# 2-mcu.net
KiCad netlist of a schematic drawn in Altium Designer
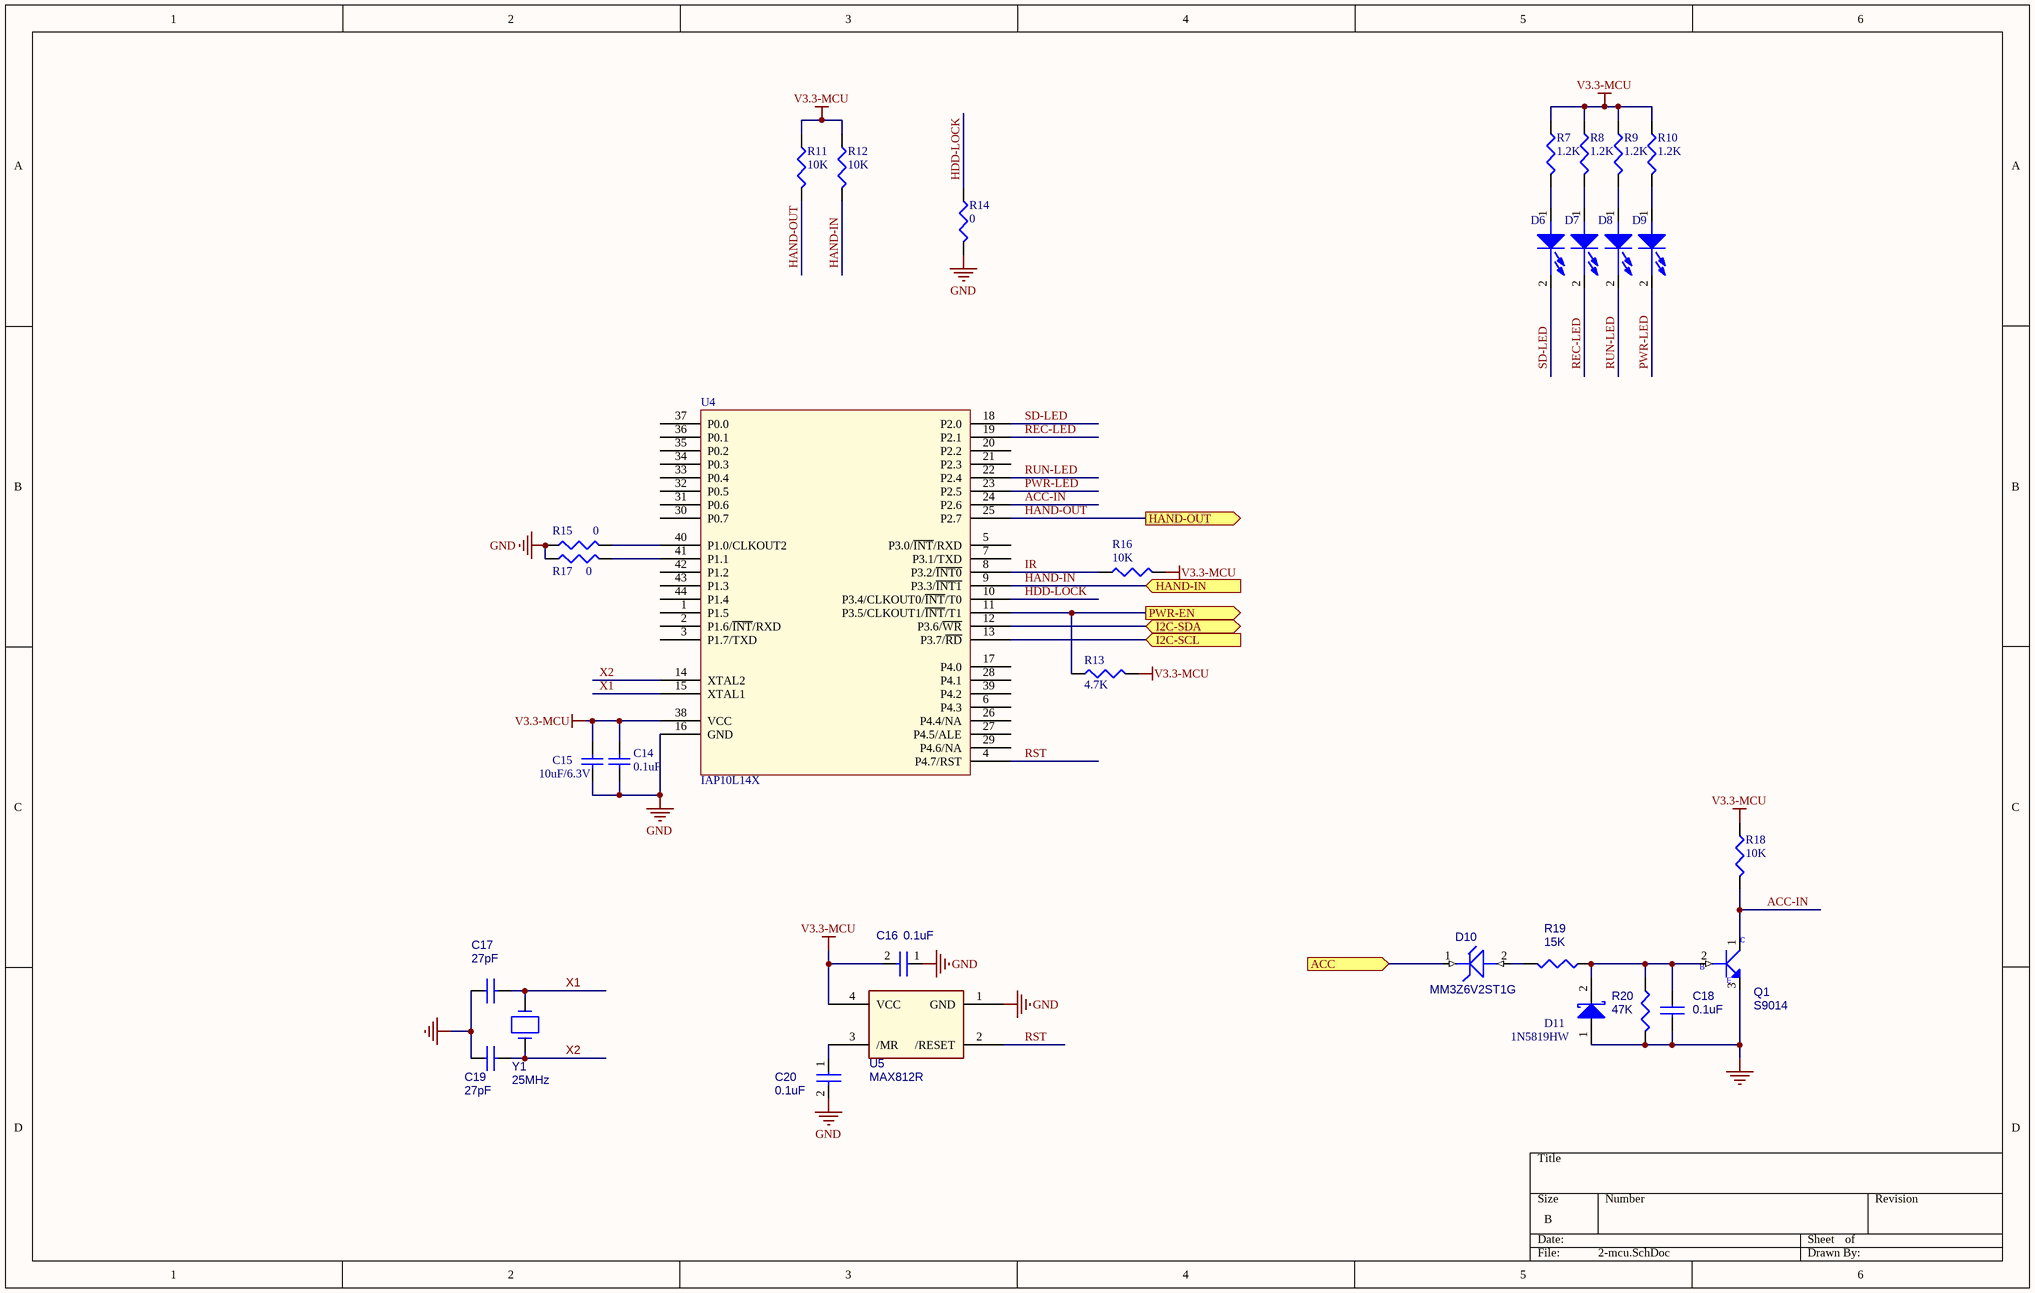
[diagram p0: 2-mcu.SchDoc]

(export (version "E")
  (design (tool "Eeschema 10.0.6"))
  (components
    (comp (ref "C14")
      (value "0.1uF")
      (footprint "0603")
      (description "Capacitor")
      (libsource (lib "Miscellaneous Devices") (part "Cap"))
    )
    (comp (ref "C15")
      (value "10uF/6.3V")
      (footprint "0805")
      (description "Capacitor")
      (libsource (lib "Miscellaneous Devices") (part "Cap"))
    )
    (comp (ref "C16") (value "0.1uF") (libsource (lib "*") (part "CAP NP_Dup2")))
    (comp (ref "C17") (value "27pF") (libsource (lib "*") (part "CAP_Dup1")))
    (comp (ref "C18") (value "0.1uF") (libsource (lib "*") (part "CAP")))
    (comp (ref "C19") (value "27pF") (libsource (lib "*") (part "CAP_Dup1")))
    (comp (ref "C20") (value "0.1uF") (libsource (lib "*") (part "CAP NP_Dup2")))
    (comp (ref "D6") (value "LED GREEN") (footprint "LED0603") (libsource (lib "*") (part "LN01401_1")))
    (comp (ref "D7") (value "LED GREEN") (footprint "LED0603") (libsource (lib "*") (part "LN01401_1")))
    (comp (ref "D8") (value "LED GREEN") (footprint "LED0603") (libsource (lib "*") (part "LN01401_1")))
    (comp (ref "D9") (value "LED GREEN") (footprint "LED0603") (libsource (lib "*") (part "LN01401_1")))
    (comp (ref "D10")
      (value "MM3Z6V2ST1G")
      (footprint "MM3Z5V1ST1G")
      (libsource (lib "*") (part "MMGZ5231BPTLL34"))
    )
    (comp (ref "D11")
      (value "1N5819HW")
      (footprint "1N5819")
      (description "Schottky Rectifier")
      (libsource (lib "Miscellaneous Devices") (part "Diode 11DQ03"))
    )
    (comp (ref "Q1")
      (value "S9014")
      (footprint "NPN")
      (fields (field (name "PART NUMBER") "SB039040000"))
      (libsource (lib "*") (part "MMBT3904_NL_SOT23-3"))
    )
    (comp (ref "R7") (value "1.2K") (footprint "0603") (libsource (lib "*") (part "CR16-1003FM")))
    (comp (ref "R8") (value "1.2K") (footprint "0603") (libsource (lib "*") (part "CR16-1003FM")))
    (comp (ref "R9") (value "1.2K") (footprint "0603") (libsource (lib "*") (part "CR16-1003FM")))
    (comp (ref "R10") (value "1.2K") (footprint "0603") (libsource (lib "*") (part "CR16-1003FM")))
    (comp (ref "R11") (value "10K") (footprint "0603") (libsource (lib "*") (part "CR16-1003FM")))
    (comp (ref "R12") (value "10K") (footprint "0603") (libsource (lib "*") (part "CR16-1003FM")))
    (comp (ref "R13") (value "4.7K") (footprint "0603") (libsource (lib "*") (part "CR16-1003FM")))
    (comp (ref "R14") (value "0") (footprint "0603") (libsource (lib "*") (part "CR16-1003FM")))
    (comp (ref "R15") (value "0") (footprint "0603") (libsource (lib "*") (part "CR16-1003FM")))
    (comp (ref "R16") (value "10K") (footprint "0603") (libsource (lib "*") (part "CR16-1003FM")))
    (comp (ref "R17") (value "0") (footprint "0603") (libsource (lib "*") (part "CR16-1003FM")))
    (comp (ref "R18") (value "10K") (footprint "0603") (libsource (lib "*") (part "CR16-1003FM")))
    (comp (ref "R19") (value "15K") (libsource (lib "*") (part "R")))
    (comp (ref "R20") (value "47K") (libsource (lib "*") (part "R")))
    (comp (ref "U4") (value "IAP10L14X") (footprint "LQFP44") (libsource (lib "Schlib") (part "IAP10L14X")))
    (comp (ref "U5") (value "MAX812R") (libsource (lib "*") (part "MAX811")))
    (comp (ref "Y1") (value "25MHz") (libsource (lib "*") (part "CRYSTAL")))
  )
  (nets
    (net (code "1") (name "/ACC") (class "Default")
      (node (ref "D10") (pin "1") (pinfunction "1_1") (pintype "input"))
    )
    (net (code "2") (name "/ACC-IN") (class "Default")
      (node (ref "Q1") (pin "1") (pinfunction "COLLECTOR_1") (pintype "passive"))
      (node (ref "R18") (pin "2") (pinfunction "2_2") (pintype "passive"))
      (node (ref "U4") (pin "24") (pinfunction "P2.6_24") (pintype "passive"))
    )
    (net (code "3") (name "/HAND-IN") (class "Default")
      (node (ref "R12") (pin "2") (pinfunction "2_2") (pintype "passive"))
      (node (ref "U4") (pin "9") (pinfunction "P3.3/~{INT1}_9") (pintype "passive"))
    )
    (net (code "4") (name "/HAND-OUT") (class "Default")
      (node (ref "R11") (pin "2") (pinfunction "2_2") (pintype "passive"))
      (node (ref "U4") (pin "25") (pinfunction "P2.7_25") (pintype "passive"))
    )
    (net (code "5") (name "/HDD-LOCK") (class "Default")
      (node (ref "R14") (pin "1") (pinfunction "1_1") (pintype "passive"))
      (node (ref "U4") (pin "10") (pinfunction "P3.4/CLKOUT0/~{INT}/T0_10") (pintype "passive"))
    )
    (net (code "6") (name "/I2C-SCL") (class "Default")
      (node (ref "U4") (pin "13") (pinfunction "P3.7/~{RD}_13") (pintype "passive"))
    )
    (net (code "7") (name "/I2C-SDA") (class "Default")
      (node (ref "U4") (pin "12") (pinfunction "P3.6/~{WR}_12") (pintype "passive"))
    )
    (net (code "8") (name "/IR") (class "Default")
      (node (ref "R16") (pin "1") (pinfunction "1_1") (pintype "passive"))
      (node (ref "U4") (pin "8") (pinfunction "P3.2/~{INT0}_8") (pintype "passive"))
    )
    (net (code "9") (name "/PWR-EN") (class "Default")
      (node (ref "R13") (pin "1") (pinfunction "1_1") (pintype "passive"))
      (node (ref "U4") (pin "11") (pinfunction "P3.5/CLKOUT1/~{INT}/T1_11") (pintype "passive"))
    )
    (net (code "10") (name "/PWR-LED") (class "Default")
      (node (ref "D9") (pin "2") (pinfunction "CATHODE_2") (pintype "passive"))
      (node (ref "U4") (pin "23") (pinfunction "P2.5_23") (pintype "passive"))
    )
    (net (code "11") (name "/REC-LED") (class "Default")
      (node (ref "D7") (pin "2") (pinfunction "CATHODE_2") (pintype "passive"))
      (node (ref "U4") (pin "19") (pinfunction "P2.1_19") (pintype "passive"))
    )
    (net (code "12") (name "/RST") (class "Default")
      (node (ref "U4") (pin "4") (pinfunction "P4.7/RST_4") (pintype "passive"))
      (node (ref "U5") (pin "2") (pinfunction "/RESET_2") (pintype "passive"))
    )
    (net (code "13") (name "/RUN-LED") (class "Default")
      (node (ref "D8") (pin "2") (pinfunction "CATHODE_2") (pintype "passive"))
      (node (ref "U4") (pin "22") (pinfunction "P2.4_22") (pintype "passive"))
    )
    (net (code "14") (name "/SD-LED") (class "Default")
      (node (ref "D6") (pin "2") (pinfunction "CATHODE_2") (pintype "passive"))
      (node (ref "U4") (pin "18") (pinfunction "P2.0_18") (pintype "passive"))
    )
    (net (code "15") (name "/X1") (class "Default")
      (node (ref "C17") (pin "2") (pinfunction "2_2") (pintype "passive"))
      (node (ref "U4") (pin "15") (pinfunction "XTAL1_15") (pintype "passive"))
      (node (ref "Y1") (pin "2") (pinfunction "2_2") (pintype "passive"))
    )
    (net (code "16") (name "/X2") (class "Default")
      (node (ref "C19") (pin "2") (pinfunction "2_2") (pintype "passive"))
      (node (ref "U4") (pin "14") (pinfunction "XTAL2_14") (pintype "passive"))
      (node (ref "Y1") (pin "1") (pinfunction "1_1") (pintype "passive"))
    )
    (net (code "17") (name "GND") (class "Default")
      (node (ref "C14") (pin "1") (pinfunction "1_1") (pintype "passive"))
      (node (ref "C15") (pin "1") (pinfunction "1_1") (pintype "passive"))
      (node (ref "C16") (pin "1") (pinfunction "1_1") (pintype "passive"))
      (node (ref "C17") (pin "1") (pinfunction "1_1") (pintype "passive"))
      (node (ref "C18") (pin "2") (pinfunction "2_2") (pintype "passive"))
      (node (ref "C19") (pin "1") (pinfunction "1_1") (pintype "passive"))
      (node (ref "C20") (pin "2") (pinfunction "2_2") (pintype "passive"))
      (node (ref "D11") (pin "1") (pinfunction "A_1") (pintype "passive"))
      (node (ref "Q1") (pin "3") (pinfunction "EMITTER_3") (pintype "passive"))
      (node (ref "R14") (pin "2") (pinfunction "2_2") (pintype "passive"))
      (node (ref "R15") (pin "1") (pinfunction "1_1") (pintype "passive"))
      (node (ref "R17") (pin "1") (pinfunction "1_1") (pintype "passive"))
      (node (ref "R20") (pin "2") (pinfunction "2_2") (pintype "passive"))
      (node (ref "U4") (pin "16") (pinfunction "GND_16") (pintype "passive"))
      (node (ref "U5") (pin "1") (pinfunction "GND_1") (pintype "passive"))
    )
    (net (code "18") (name "Net-(D6-ANODE)") (class "Default")
      (node (ref "D6") (pin "1") (pinfunction "ANODE_1") (pintype "passive"))
      (node (ref "R7") (pin "2") (pinfunction "2_2") (pintype "passive"))
    )
    (net (code "19") (name "Net-(D7-ANODE)") (class "Default")
      (node (ref "D7") (pin "1") (pinfunction "ANODE_1") (pintype "passive"))
      (node (ref "R8") (pin "2") (pinfunction "2_2") (pintype "passive"))
    )
    (net (code "20") (name "Net-(D8-ANODE)") (class "Default")
      (node (ref "D8") (pin "1") (pinfunction "ANODE_1") (pintype "passive"))
      (node (ref "R9") (pin "2") (pinfunction "2_2") (pintype "passive"))
    )
    (net (code "21") (name "Net-(D9-ANODE)") (class "Default")
      (node (ref "D9") (pin "1") (pinfunction "ANODE_1") (pintype "passive"))
      (node (ref "R10") (pin "2") (pinfunction "2_2") (pintype "passive"))
    )
    (net (code "22") (name "Net-(D10-Pad2)") (class "Default")
      (node (ref "D10") (pin "2") (pinfunction "2_2") (pintype "input"))
      (node (ref "R19") (pin "2") (pinfunction "2_2") (pintype "passive"))
    )
    (net (code "23") (name "Net-(D11-K)") (class "Default")
      (node (ref "C18") (pin "1") (pinfunction "1_1") (pintype "passive"))
      (node (ref "D11") (pin "2") (pinfunction "K_2") (pintype "passive"))
      (node (ref "Q1") (pin "2") (pinfunction "BASE_2") (pintype "input"))
      (node (ref "R19") (pin "1") (pinfunction "1_1") (pintype "passive"))
      (node (ref "R20") (pin "1") (pinfunction "1_1") (pintype "passive"))
    )
    (net (code "24") (name "Net-(U4-P1.0{slash}CLKOUT2)") (class "Default")
      (node (ref "R15") (pin "2") (pinfunction "2_2") (pintype "passive"))
      (node (ref "U4") (pin "40") (pinfunction "P1.0/CLKOUT2_40") (pintype "passive"))
    )
    (net (code "25") (name "Net-(U4-P1.1)") (class "Default")
      (node (ref "R17") (pin "2") (pinfunction "2_2") (pintype "passive"))
      (node (ref "U4") (pin "41") (pinfunction "P1.1_41") (pintype "passive"))
    )
    (net (code "26") (name "Net-(U5-{slash}MR)") (class "Default")
      (node (ref "C20") (pin "1") (pinfunction "1_1") (pintype "passive"))
      (node (ref "U5") (pin "3") (pinfunction "/MR_3") (pintype "passive"))
    )
    (net (code "27") (name "V3.3-MCU") (class "Default")
      (node (ref "C14") (pin "2") (pinfunction "2_2") (pintype "passive"))
      (node (ref "C15") (pin "2") (pinfunction "2_2") (pintype "passive"))
      (node (ref "C16") (pin "2") (pinfunction "2_2") (pintype "passive"))
      (node (ref "R10") (pin "1") (pinfunction "1_1") (pintype "passive"))
      (node (ref "R11") (pin "1") (pinfunction "1_1") (pintype "passive"))
      (node (ref "R12") (pin "1") (pinfunction "1_1") (pintype "passive"))
      (node (ref "R13") (pin "2") (pinfunction "2_2") (pintype "passive"))
      (node (ref "R16") (pin "2") (pinfunction "2_2") (pintype "passive"))
      (node (ref "R18") (pin "1") (pinfunction "1_1") (pintype "passive"))
      (node (ref "R7") (pin "1") (pinfunction "1_1") (pintype "passive"))
      (node (ref "R8") (pin "1") (pinfunction "1_1") (pintype "passive"))
      (node (ref "R9") (pin "1") (pinfunction "1_1") (pintype "passive"))
      (node (ref "U4") (pin "38") (pinfunction "VCC_38") (pintype "passive"))
      (node (ref "U5") (pin "4") (pinfunction "VCC_4") (pintype "passive"))
    )
    (net (code "28") (name "unconnected-(U4-P0.0-Pad37)") (class "Default")
      (node (ref "U4") (pin "37") (pinfunction "P0.0_37") (pintype "passive"))
    )
    (net (code "29") (name "unconnected-(U4-P0.1-Pad36)") (class "Default")
      (node (ref "U4") (pin "36") (pinfunction "P0.1_36") (pintype "passive"))
    )
    (net (code "30") (name "unconnected-(U4-P0.2-Pad35)") (class "Default")
      (node (ref "U4") (pin "35") (pinfunction "P0.2_35") (pintype "passive"))
    )
    (net (code "31") (name "unconnected-(U4-P0.3-Pad34)") (class "Default")
      (node (ref "U4") (pin "34") (pinfunction "P0.3_34") (pintype "passive"))
    )
    (net (code "32") (name "unconnected-(U4-P0.4-Pad33)") (class "Default")
      (node (ref "U4") (pin "33") (pinfunction "P0.4_33") (pintype "passive"))
    )
    (net (code "33") (name "unconnected-(U4-P0.5-Pad32)") (class "Default")
      (node (ref "U4") (pin "32") (pinfunction "P0.5_32") (pintype "passive"))
    )
    (net (code "34") (name "unconnected-(U4-P0.6-Pad31)") (class "Default")
      (node (ref "U4") (pin "31") (pinfunction "P0.6_31") (pintype "passive"))
    )
    (net (code "35") (name "unconnected-(U4-P0.7-Pad30)") (class "Default")
      (node (ref "U4") (pin "30") (pinfunction "P0.7_30") (pintype "passive"))
    )
    (net (code "36") (name "unconnected-(U4-P1.2-Pad42)") (class "Default")
      (node (ref "U4") (pin "42") (pinfunction "P1.2_42") (pintype "passive"))
    )
    (net (code "37") (name "unconnected-(U4-P1.3-Pad43)") (class "Default")
      (node (ref "U4") (pin "43") (pinfunction "P1.3_43") (pintype "passive"))
    )
    (net (code "38") (name "unconnected-(U4-P1.4-Pad44)") (class "Default")
      (node (ref "U4") (pin "44") (pinfunction "P1.4_44") (pintype "passive"))
    )
    (net (code "39") (name "unconnected-(U4-P1.5-Pad1)") (class "Default")
      (node (ref "U4") (pin "1") (pinfunction "P1.5_1") (pintype "passive"))
    )
    (net (code "40") (name "unconnected-(U4-P1.6{slash}~{INT}{slash}RXD-Pad2)") (class "Default")
      (node (ref "U4") (pin "2") (pinfunction "P1.6/~{INT}/RXD_2") (pintype "passive"))
    )
    (net (code "41") (name "unconnected-(U4-P1.7{slash}TXD-Pad3)") (class "Default")
      (node (ref "U4") (pin "3") (pinfunction "P1.7/TXD_3") (pintype "passive"))
    )
    (net (code "42") (name "unconnected-(U4-P2.2-Pad20)") (class "Default")
      (node (ref "U4") (pin "20") (pinfunction "P2.2_20") (pintype "passive"))
    )
    (net (code "43") (name "unconnected-(U4-P2.3-Pad21)") (class "Default")
      (node (ref "U4") (pin "21") (pinfunction "P2.3_21") (pintype "passive"))
    )
    (net (code "44") (name "unconnected-(U4-P3.0{slash}~{INT}{slash}RXD-Pad5)") (class "Default")
      (node (ref "U4") (pin "5") (pinfunction "P3.0/~{INT}/RXD_5") (pintype "passive"))
    )
    (net (code "45") (name "unconnected-(U4-P3.1{slash}TXD-Pad7)") (class "Default")
      (node (ref "U4") (pin "7") (pinfunction "P3.1/TXD_7") (pintype "passive"))
    )
    (net (code "46") (name "unconnected-(U4-P4.0-Pad17)") (class "Default")
      (node (ref "U4") (pin "17") (pinfunction "P4.0_17") (pintype "passive"))
    )
    (net (code "47") (name "unconnected-(U4-P4.1-Pad28)") (class "Default")
      (node (ref "U4") (pin "28") (pinfunction "P4.1_28") (pintype "passive"))
    )
    (net (code "48") (name "unconnected-(U4-P4.2-Pad39)") (class "Default")
      (node (ref "U4") (pin "39") (pinfunction "P4.2_39") (pintype "passive"))
    )
    (net (code "49") (name "unconnected-(U4-P4.3-Pad6)") (class "Default")
      (node (ref "U4") (pin "6") (pinfunction "P4.3_6") (pintype "passive"))
    )
    (net (code "50") (name "unconnected-(U4-P4.4{slash}NA-Pad26)") (class "Default")
      (node (ref "U4") (pin "26") (pinfunction "P4.4/NA_26") (pintype "passive"))
    )
    (net (code "51") (name "unconnected-(U4-P4.5{slash}ALE-Pad27)") (class "Default")
      (node (ref "U4") (pin "27") (pinfunction "P4.5/ALE_27") (pintype "passive"))
    )
    (net (code "52") (name "unconnected-(U4-P4.6{slash}NA-Pad29)") (class "Default")
      (node (ref "U4") (pin "29") (pinfunction "P4.6/NA_29") (pintype "passive"))
    )
  )
)
